# barBloom3.net
KiCad netlist of a schematic drawn in EAGLE
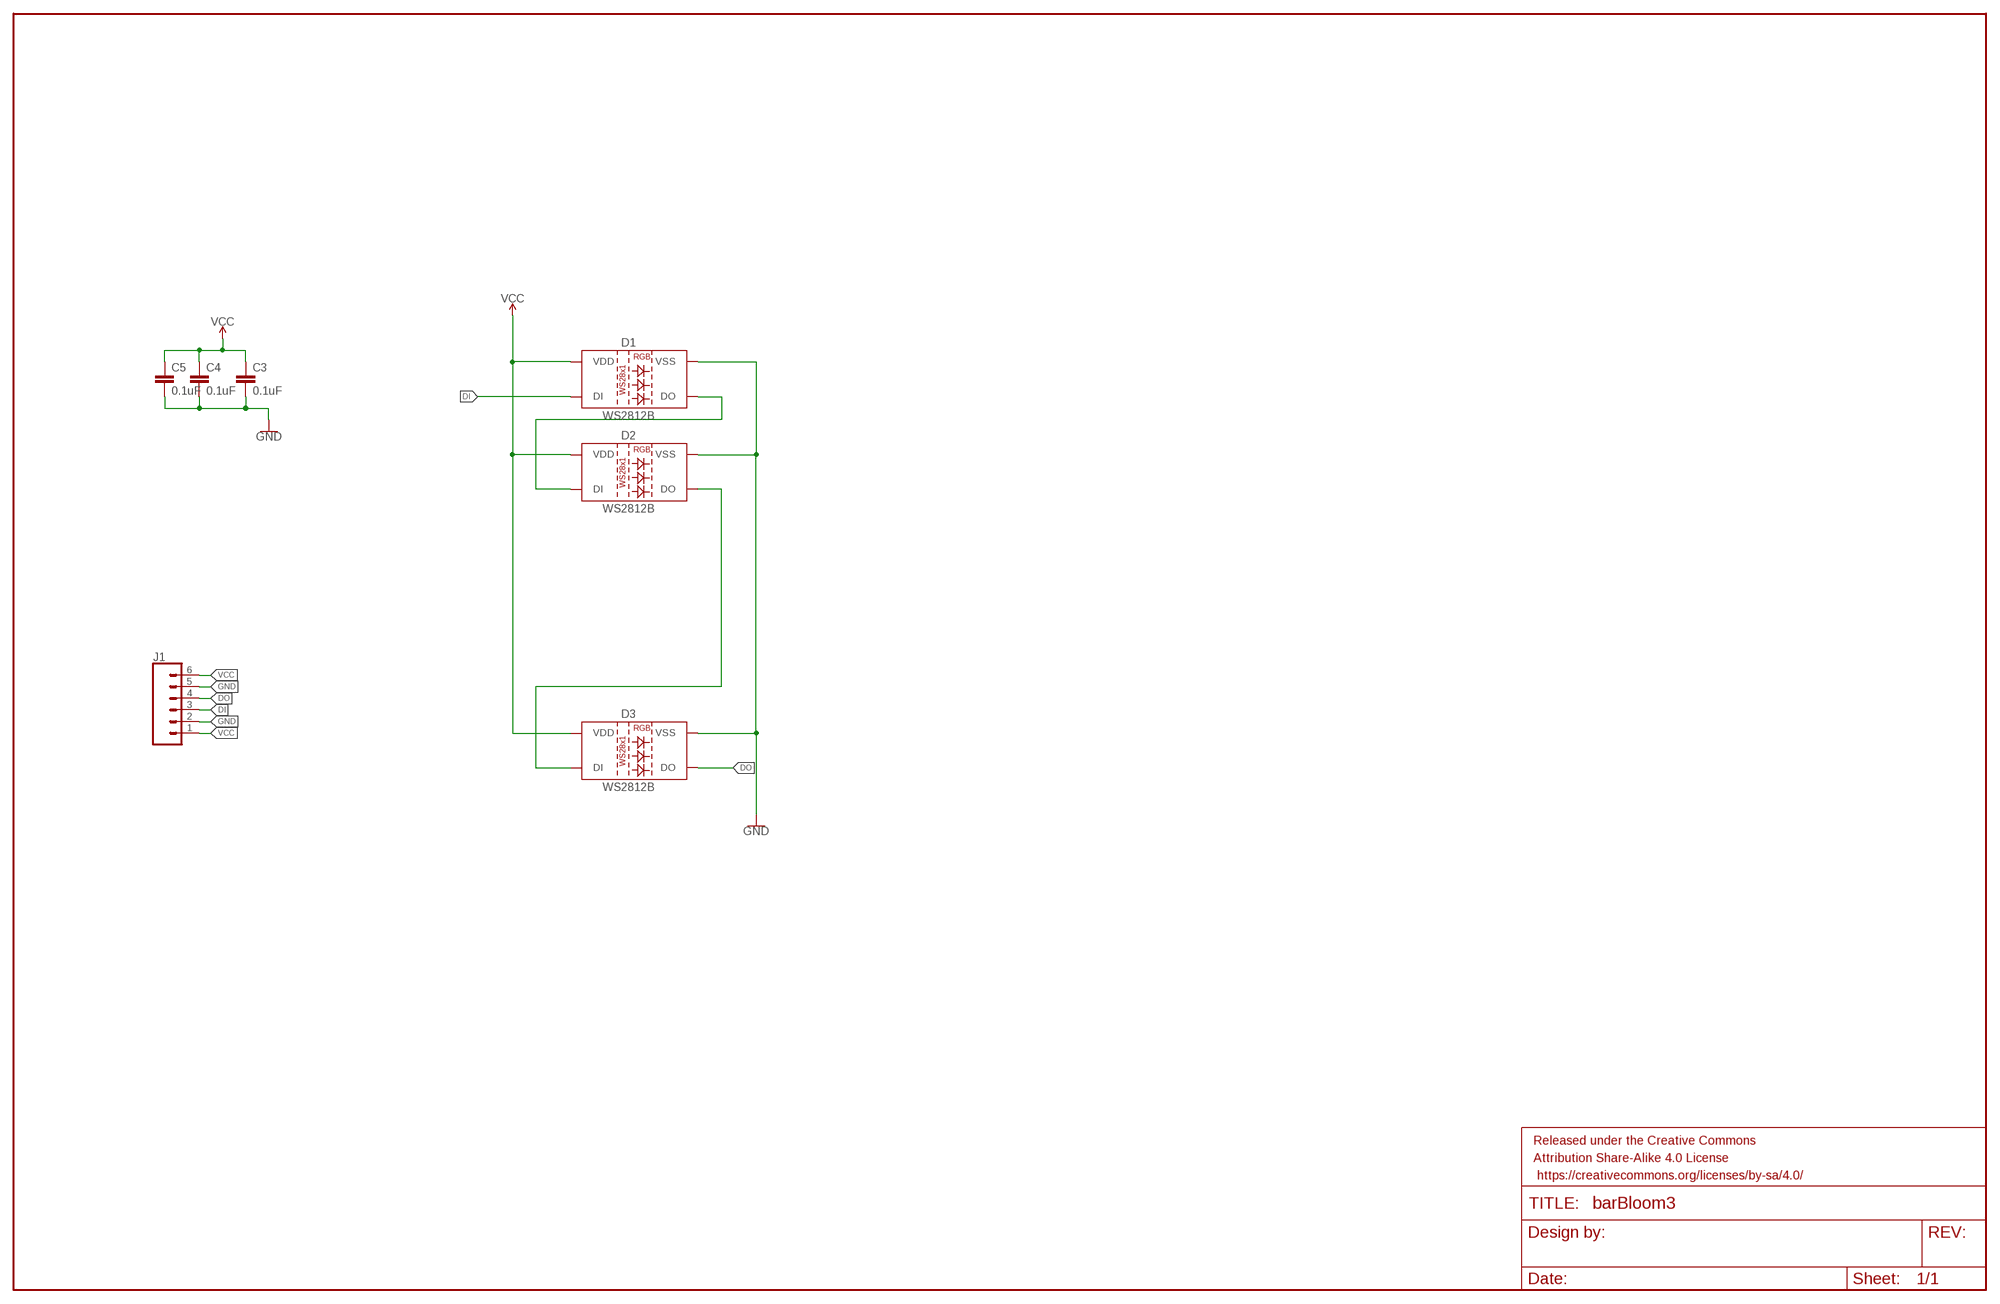
[diagram p0: schematic, sheet 1]

(export (version "E")
  (design (tool "Eeschema 10.0.6"))
  (components
    (comp (ref "C3")
      (value "0.1uF")
      (footprint "eagle-import:0603")
      (libsource (lib "eagle-import") (part "0.1UF-0603-25V-(+80/-20%)"))
    )
    (comp (ref "C4")
      (value "0.1uF")
      (footprint "eagle-import:0603")
      (libsource (lib "eagle-import") (part "0.1UF-0603-25V-(+80/-20%)"))
    )
    (comp (ref "C5")
      (value "0.1uF")
      (footprint "eagle-import:0603")
      (libsource (lib "eagle-import") (part "0.1UF-0603-25V-(+80/-20%)"))
    )
    (comp (ref "D1")
      (value "WS2812B")
      (footprint "eagle-import:WS2812B")
      (libsource (lib "eagle-import") (part "WS2812B"))
    )
    (comp (ref "D2")
      (value "WS2812B")
      (footprint "eagle-import:WS2812B")
      (libsource (lib "eagle-import") (part "WS2812B"))
    )
    (comp (ref "D3")
      (value "WS2812B")
      (footprint "eagle-import:WS2812B")
      (libsource (lib "eagle-import") (part "WS2812B"))
    )
    (comp (ref "FRAME1")
      (value "FRAME-LEDGER")
      (footprint "eagle-import:CREATIVE_COMMONS")
      (libsource (lib "eagle-import") (part "FRAME-LEDGER"))
    )
    (comp (ref "J1")
      (value "CONN_06SMD-STRAIGHT-ALT-FEMALE")
      (footprint "eagle-import:1X06_SMD_STRAIGHT_ALT")
      (libsource (lib "eagle-import") (part "CONN_06SMD-STRAIGHT-ALT-FEMALE"))
    )
  )
  (nets
    (net (code "1") (name "DI") (class "Default")
      (node (ref "D1") (pin "4") (pinfunction "DI_4") (pintype "bidirectional"))
      (node (ref "J1") (pin "3") (pinfunction "3_3") (pintype "passive"))
    )
    (net (code "2") (name "DO") (class "Default")
      (node (ref "D3") (pin "2") (pinfunction "DO_2") (pintype "bidirectional"))
      (node (ref "J1") (pin "4") (pinfunction "4_4") (pintype "passive"))
    )
    (net (code "3") (name "GND") (class "Default")
      (node (ref "C3") (pin "2") (pinfunction "2_2") (pintype "passive"))
      (node (ref "C4") (pin "2") (pinfunction "2_2") (pintype "passive"))
      (node (ref "C5") (pin "2") (pinfunction "2_2") (pintype "passive"))
      (node (ref "D1") (pin "3") (pinfunction "VSS_3") (pintype "bidirectional"))
      (node (ref "D2") (pin "3") (pinfunction "VSS_3") (pintype "bidirectional"))
      (node (ref "D3") (pin "3") (pinfunction "VSS_3") (pintype "bidirectional"))
      (node (ref "J1") (pin "2") (pinfunction "2_2") (pintype "passive"))
      (node (ref "J1") (pin "5") (pinfunction "5_5") (pintype "passive"))
    )
    (net (code "4") (name "Net-(D1-DO)") (class "Default")
      (node (ref "D1") (pin "2") (pinfunction "DO_2") (pintype "bidirectional"))
      (node (ref "D2") (pin "4") (pinfunction "DI_4") (pintype "bidirectional"))
    )
    (net (code "5") (name "Net-(D2-DO)") (class "Default")
      (node (ref "D2") (pin "2") (pinfunction "DO_2") (pintype "bidirectional"))
      (node (ref "D3") (pin "4") (pinfunction "DI_4") (pintype "bidirectional"))
    )
    (net (code "6") (name "VCC") (class "Default")
      (node (ref "C3") (pin "1") (pinfunction "1_1") (pintype "passive"))
      (node (ref "C4") (pin "1") (pinfunction "1_1") (pintype "passive"))
      (node (ref "C5") (pin "1") (pinfunction "1_1") (pintype "passive"))
      (node (ref "D1") (pin "1") (pinfunction "VDD_1") (pintype "bidirectional"))
      (node (ref "D2") (pin "1") (pinfunction "VDD_1") (pintype "bidirectional"))
      (node (ref "D3") (pin "1") (pinfunction "VDD_1") (pintype "bidirectional"))
      (node (ref "J1") (pin "1") (pinfunction "1_1") (pintype "passive"))
      (node (ref "J1") (pin "6") (pinfunction "6_6") (pintype "passive"))
    )
  )
)
